# sensor-water.net
KiCad netlist of a schematic drawn in EAGLE
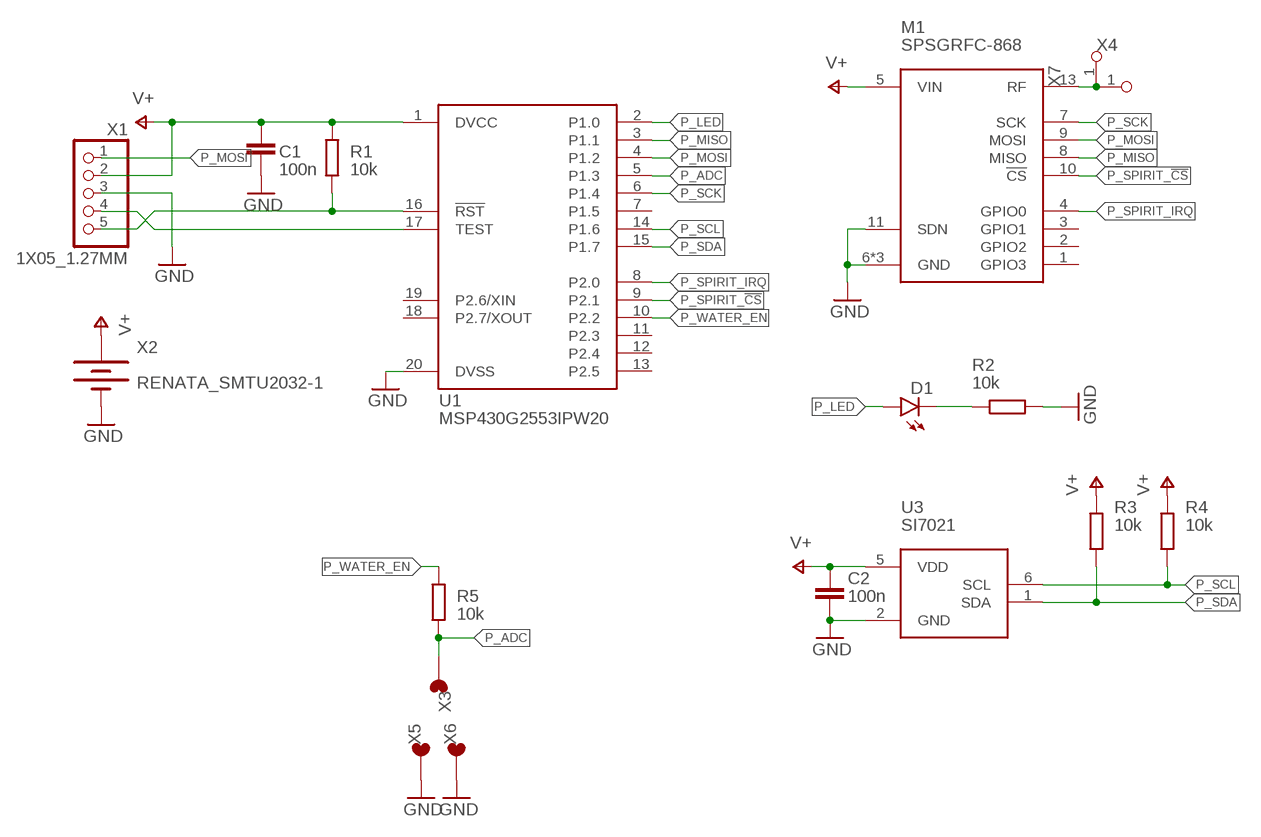
[diagram p0: schematic, sheet 1]

(export (version "E")
  (design (tool "Eeschema 10.0.6"))
  (components
    (comp (ref "C1")
      (value "100n")
      (footprint "eagle-import:C0805_HAND")
      (libsource (lib "eagle-import") (part "C0805_HAND"))
    )
    (comp (ref "C2")
      (value "100n")
      (footprint "eagle-import:C0805_HAND")
      (libsource (lib "eagle-import") (part "C0805_HAND"))
    )
    (comp (ref "D1")
      (value "LEDCHIPLED_0805")
      (footprint "eagle-import:CHIPLED_0805")
      (libsource (lib "eagle-import") (part "LEDCHIPLED_0805"))
    )
    (comp (ref "M1")
      (value "SPSGRFC-868")
      (footprint "eagle-import:SPSGRFC-868")
      (libsource (lib "eagle-import") (part "SPSGRFC-868"))
    )
    (comp (ref "R1")
      (value "10k")
      (footprint "eagle-import:R0805_HAND")
      (libsource (lib "eagle-import") (part "R0805_HAND"))
    )
    (comp (ref "R2")
      (value "10k")
      (footprint "eagle-import:R0805_HAND")
      (libsource (lib "eagle-import") (part "R0805_HAND"))
    )
    (comp (ref "R3")
      (value "10k")
      (footprint "eagle-import:R0805_HAND")
      (libsource (lib "eagle-import") (part "R0805_HAND"))
    )
    (comp (ref "R4")
      (value "10k")
      (footprint "eagle-import:R0805_HAND")
      (libsource (lib "eagle-import") (part "R0805_HAND"))
    )
    (comp (ref "R5")
      (value "10k")
      (footprint "eagle-import:R0805_HAND")
      (libsource (lib "eagle-import") (part "R0805_HAND"))
    )
    (comp (ref "U1")
      (value "MSP430G2553IPW20")
      (footprint "eagle-import:PW20")
      (libsource (lib "eagle-import") (part "MSP430G2553IPW20"))
    )
    (comp (ref "U3")
      (value "SI7021")
      (footprint "eagle-import:DFN6-3X3")
      (libsource (lib "eagle-import") (part "SI7021"))
    )
    (comp (ref "X1")
      (value "1X05_1.27MM")
      (footprint "eagle-import:1X05_1.27MM")
      (libsource (lib "eagle-import") (part "1X05_1.27MM"))
    )
    (comp (ref "X2")
      (value "RENATA_SMTU2032-1")
      (footprint "eagle-import:RENATA_SMTU2032-1")
      (libsource (lib "eagle-import") (part "RENATA_SMTU2032-1"))
    )
    (comp (ref "X3")
      (value "WASSERW_FOOTS")
      (footprint "eagle-import:WASSERW_FOOTS")
      (libsource (lib "eagle-import") (part "WASSERW_FOOTS"))
    )
    (comp (ref "X4")
      (value "PINHD_1_RND")
      (footprint "eagle-import:1X01_NOSILK")
      (libsource (lib "eagle-import") (part "PINHD_1_RND"))
    )
    (comp (ref "X5")
      (value "WASSERW_FOOTS")
      (footprint "eagle-import:WASSERW_FOOTS")
      (libsource (lib "eagle-import") (part "WASSERW_FOOTS"))
    )
    (comp (ref "X6")
      (value "WASSERW_FOOTS")
      (footprint "eagle-import:WASSERW_FOOTS")
      (libsource (lib "eagle-import") (part "WASSERW_FOOTS"))
    )
    (comp (ref "X7")
      (value "PINHD_1_RND")
      (footprint "eagle-import:1X01_NOSILK")
      (libsource (lib "eagle-import") (part "PINHD_1_RND"))
    )
  )
  (nets
    (net (code "1") (name "/P_SPIRIT_~{CS}") (class "Default")
      (node (ref "M1") (pin "10") (pinfunction "~{CS}_10") (pintype "input"))
      (node (ref "U1") (pin "9") (pinfunction "P2.1_9") (pintype "bidirectional"))
    )
    (net (code "2") (name "GND") (class "Default")
      (node (ref "C1") (pin "2") (pinfunction "2_2") (pintype "passive"))
      (node (ref "C2") (pin "2") (pinfunction "2_2") (pintype "passive"))
      (node (ref "M1") (pin "11") (pinfunction "SDN_11") (pintype "input"))
      (node (ref "M1") (pin "12") (pinfunction "GND_12") (pintype "power_in"))
      (node (ref "M1") (pin "14") (pinfunction "GND_14") (pintype "power_in"))
      (node (ref "M1") (pin "6") (pinfunction "GND_6") (pintype "power_in"))
      (node (ref "R2") (pin "2") (pinfunction "2_2") (pintype "passive"))
      (node (ref "U1") (pin "20") (pinfunction "DVSS_20") (pintype "bidirectional"))
      (node (ref "U3") (pin "2") (pinfunction "GND_2") (pintype "power_in"))
      (node (ref "X1") (pin "3") (pinfunction "3_3") (pintype "passive"))
      (node (ref "X2") (pin "2") (pinfunction "-_2") (pintype "power_in"))
      (node (ref "X5") (pin "1") (pinfunction "1_1") (pintype "passive"))
      (node (ref "X6") (pin "1") (pinfunction "1_1") (pintype "passive"))
    )
    (net (code "3") (name "Net-(D1-PadC)") (class "Default")
      (node (ref "D1") (pin "C") (pinfunction "C_C") (pintype "passive"))
      (node (ref "R2") (pin "1") (pinfunction "1_1") (pintype "passive"))
    )
    (net (code "4") (name "Net-(M1-RF)") (class "Default")
      (node (ref "M1") (pin "13") (pinfunction "RF_13") (pintype "bidirectional"))
      (node (ref "X4") (pin "1") (pinfunction "1_1") (pintype "passive"))
      (node (ref "X7") (pin "1") (pinfunction "1_1") (pintype "passive"))
    )
    (net (code "5") (name "Net-(U1-TEST)") (class "Default")
      (node (ref "U1") (pin "17") (pinfunction "TEST_17") (pintype "bidirectional"))
      (node (ref "X1") (pin "4") (pinfunction "4_4") (pintype "passive"))
    )
    (net (code "6") (name "Net-(U1-~{RST})") (class "Default")
      (node (ref "R1") (pin "1") (pinfunction "1_1") (pintype "passive"))
      (node (ref "U1") (pin "16") (pinfunction "~{RST}_16") (pintype "bidirectional"))
      (node (ref "X1") (pin "5") (pinfunction "5_5") (pintype "passive"))
    )
    (net (code "7") (name "P_ADC") (class "Default")
      (node (ref "R5") (pin "1") (pinfunction "1_1") (pintype "passive"))
      (node (ref "U1") (pin "5") (pinfunction "P1.3_5") (pintype "bidirectional"))
      (node (ref "X3") (pin "1") (pinfunction "1_1") (pintype "passive"))
    )
    (net (code "8") (name "P_LED") (class "Default")
      (node (ref "D1") (pin "A") (pinfunction "A_A") (pintype "passive"))
      (node (ref "U1") (pin "2") (pinfunction "P1.0_2") (pintype "bidirectional"))
    )
    (net (code "9") (name "P_MISO") (class "Default")
      (node (ref "M1") (pin "8") (pinfunction "MISO_8") (pintype "bidirectional"))
      (node (ref "U1") (pin "3") (pinfunction "P1.1_3") (pintype "bidirectional"))
    )
    (net (code "10") (name "P_MOSI") (class "Default")
      (node (ref "M1") (pin "9") (pinfunction "MOSI_9") (pintype "input"))
      (node (ref "U1") (pin "4") (pinfunction "P1.2_4") (pintype "bidirectional"))
      (node (ref "X1") (pin "1") (pinfunction "1_1") (pintype "passive"))
    )
    (net (code "11") (name "P_SCK") (class "Default")
      (node (ref "M1") (pin "7") (pinfunction "SCK_7") (pintype "input"))
      (node (ref "U1") (pin "6") (pinfunction "P1.4_6") (pintype "bidirectional"))
    )
    (net (code "12") (name "P_SCL") (class "Default")
      (node (ref "R4") (pin "1") (pinfunction "1_1") (pintype "passive"))
      (node (ref "U1") (pin "14") (pinfunction "P1.6_14") (pintype "bidirectional"))
      (node (ref "U3") (pin "6") (pinfunction "SCL_6") (pintype "input"))
    )
    (net (code "13") (name "P_SDA") (class "Default")
      (node (ref "R3") (pin "1") (pinfunction "1_1") (pintype "passive"))
      (node (ref "U1") (pin "15") (pinfunction "P1.7_15") (pintype "bidirectional"))
      (node (ref "U3") (pin "1") (pinfunction "SDA_1") (pintype "input"))
    )
    (net (code "14") (name "P_SPIRIT_IRQ") (class "Default")
      (node (ref "M1") (pin "4") (pinfunction "GPIO0_4") (pintype "bidirectional"))
      (node (ref "U1") (pin "8") (pinfunction "P2.0_8") (pintype "bidirectional"))
    )
    (net (code "15") (name "P_WATER_EN") (class "Default")
      (node (ref "R5") (pin "2") (pinfunction "2_2") (pintype "passive"))
      (node (ref "U1") (pin "10") (pinfunction "P2.2_10") (pintype "bidirectional"))
    )
    (net (code "16") (name "V+") (class "Default")
      (node (ref "C1") (pin "1") (pinfunction "1_1") (pintype "passive"))
      (node (ref "C2") (pin "1") (pinfunction "1_1") (pintype "passive"))
      (node (ref "M1") (pin "5") (pinfunction "VIN_5") (pintype "power_in"))
      (node (ref "R1") (pin "2") (pinfunction "2_2") (pintype "passive"))
      (node (ref "R3") (pin "2") (pinfunction "2_2") (pintype "passive"))
      (node (ref "R4") (pin "2") (pinfunction "2_2") (pintype "passive"))
      (node (ref "U1") (pin "1") (pinfunction "DVCC_1") (pintype "bidirectional"))
      (node (ref "U3") (pin "5") (pinfunction "VDD_5") (pintype "input"))
      (node (ref "X1") (pin "2") (pinfunction "2_2") (pintype "passive"))
      (node (ref "X2") (pin "1") (pinfunction "+_1") (pintype "power_in"))
    )
    (net (code "17") (name "unconnected-(M1-GPIO1-Pad3)") (class "Default")
      (node (ref "M1") (pin "3") (pinfunction "GPIO1_3") (pintype "bidirectional"))
    )
    (net (code "18") (name "unconnected-(M1-GPIO2-Pad2)") (class "Default")
      (node (ref "M1") (pin "2") (pinfunction "GPIO2_2") (pintype "bidirectional"))
    )
    (net (code "19") (name "unconnected-(M1-GPIO3-Pad1)") (class "Default")
      (node (ref "M1") (pin "1") (pinfunction "GPIO3_1") (pintype "bidirectional"))
    )
    (net (code "20") (name "unconnected-(U1-P1.5-Pad7)") (class "Default")
      (node (ref "U1") (pin "7") (pinfunction "P1.5_7") (pintype "bidirectional"))
    )
    (net (code "21") (name "unconnected-(U1-P2.3-Pad11)") (class "Default")
      (node (ref "U1") (pin "11") (pinfunction "P2.3_11") (pintype "bidirectional"))
    )
    (net (code "22") (name "unconnected-(U1-P2.4-Pad12)") (class "Default")
      (node (ref "U1") (pin "12") (pinfunction "P2.4_12") (pintype "bidirectional"))
    )
    (net (code "23") (name "unconnected-(U1-P2.5-Pad13)") (class "Default")
      (node (ref "U1") (pin "13") (pinfunction "P2.5_13") (pintype "bidirectional"))
    )
    (net (code "24") (name "unconnected-(U1-P2.6{slash}XIN-Pad19)") (class "Default")
      (node (ref "U1") (pin "19") (pinfunction "P2.6/XIN_19") (pintype "bidirectional"))
    )
    (net (code "25") (name "unconnected-(U1-P2.7{slash}XOUT-Pad18)") (class "Default")
      (node (ref "U1") (pin "18") (pinfunction "P2.7/XOUT_18") (pintype "bidirectional"))
    )
  )
)
